# ProProject_STM32F103C6T6__2024-03-26.net
KiCad netlist of a schematic drawn in EasyEDA Pro
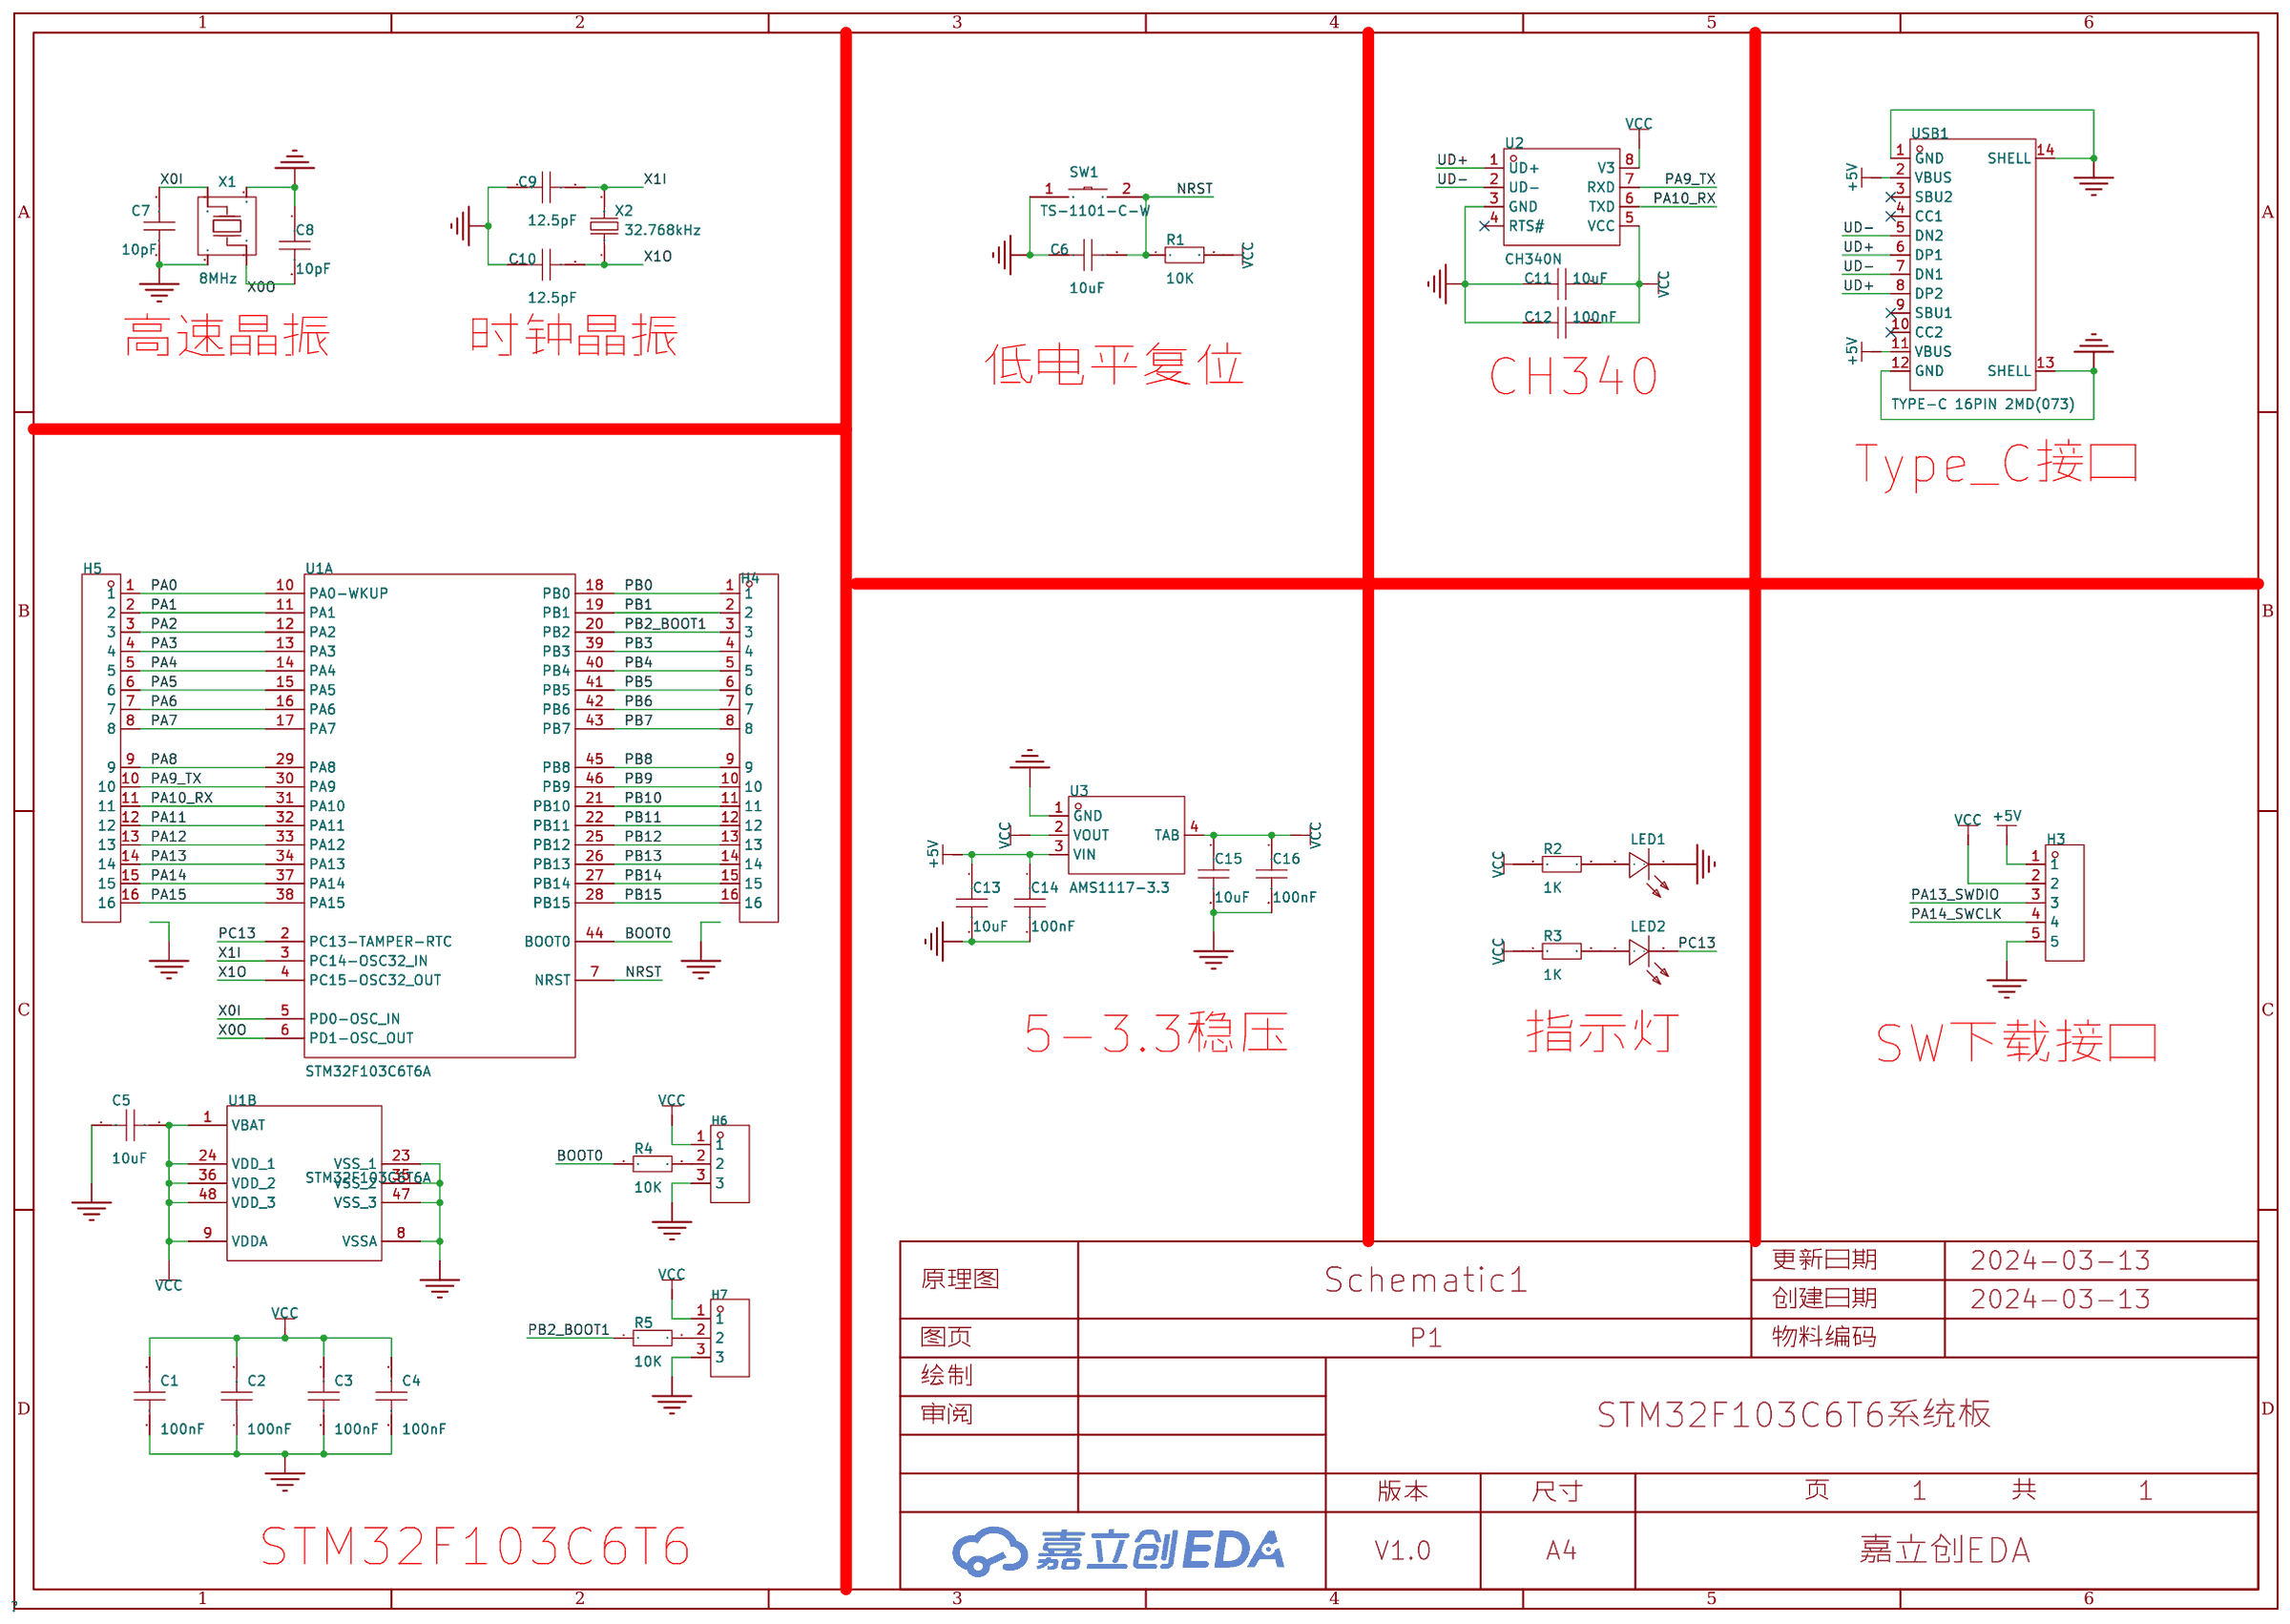
[diagram p0: schematic sheet]

(export (version "E")
  (design (tool "Eeschema 10.0.6"))
  (components
    (comp (ref "C1")
      (value "100nF")
      (footprint "easyedapro:C0603")
      (libsource (lib "easyedapro") (part "CapAcitance"))
    )
    (comp (ref "C2")
      (value "100nF")
      (footprint "easyedapro:C0603")
      (libsource (lib "easyedapro") (part "CapAcitance"))
    )
    (comp (ref "C3")
      (value "100nF")
      (footprint "easyedapro:C0603")
      (libsource (lib "easyedapro") (part "CapAcitance"))
    )
    (comp (ref "C4")
      (value "100nF")
      (footprint "easyedapro:C0603")
      (libsource (lib "easyedapro") (part "CapAcitance"))
    )
    (comp (ref "C5")
      (value "10uF")
      (footprint "easyedapro:C0603")
      (libsource (lib "easyedapro") (part "CapAcitance"))
    )
    (comp (ref "C6")
      (value "10uF")
      (footprint "easyedapro:C0603")
      (libsource (lib "easyedapro") (part "CapAcitance"))
    )
    (comp (ref "C7")
      (value "10pF")
      (footprint "easyedapro:C0603")
      (libsource (lib "easyedapro") (part "CapAcitance"))
    )
    (comp (ref "C8")
      (value "10pF")
      (footprint "easyedapro:C0603")
      (libsource (lib "easyedapro") (part "CapAcitance"))
    )
    (comp (ref "C9")
      (value "12.5pF")
      (footprint "easyedapro:C0603")
      (libsource (lib "easyedapro") (part "CapAcitance"))
    )
    (comp (ref "C10")
      (value "12.5pF")
      (footprint "easyedapro:C0603")
      (libsource (lib "easyedapro") (part "CapAcitance"))
    )
    (comp (ref "C11")
      (value "10uF")
      (footprint "easyedapro:C0603")
      (libsource (lib "easyedapro") (part "CapAcitance"))
    )
    (comp (ref "C12")
      (value "100nF")
      (footprint "easyedapro:C0603")
      (libsource (lib "easyedapro") (part "CapAcitance"))
    )
    (comp (ref "C13")
      (value "10uF")
      (footprint "easyedapro:C0603")
      (libsource (lib "easyedapro") (part "CapAcitance"))
    )
    (comp (ref "C14")
      (value "100nF")
      (footprint "easyedapro:C0603")
      (libsource (lib "easyedapro") (part "CapAcitance"))
    )
    (comp (ref "C15")
      (value "10uF")
      (footprint "easyedapro:C0603")
      (libsource (lib "easyedapro") (part "CapAcitance"))
    )
    (comp (ref "C16")
      (value "100nF")
      (footprint "easyedapro:C0603")
      (libsource (lib "easyedapro") (part "CapAcitance"))
    )
    (comp (ref "H3")
      (value "PZ254-1-05-W-8.5")
      (footprint "easyedapro:HDR-TH_5P-P2.54-H-M-W10.4-N")
      (fields (field (name "Manufacturer") "HCTL(华灿天禄)"))
      (libsource (lib "easyedapro") (part "PZ254-1-05-W-8.5"))
    )
    (comp (ref "H4")
      (value "X6511WV-20H-C60D30")
      (footprint "easyedapro:HDR-TH_20P-P2.54-V-M")
      (fields (field (name "Manufacturer") "XKB Connection(中国星坤)"))
      (libsource (lib "easyedapro") (part "X6511WV-20H-C30D60"))
    )
    (comp (ref "H5")
      (value "X6511WV-20H-C60D30")
      (footprint "easyedapro:HDR-TH_20P-P2.54-V-M")
      (fields (field (name "Manufacturer") "XKB Connection(中国星坤)"))
      (libsource (lib "easyedapro") (part "X6511WV-20H-C30D60"))
    )
    (comp (ref "H6")
      (value "PZ254V-11-03P")
      (footprint "easyedapro:HDR-TH_3P-P2.54-V-M")
      (fields (field (name "Manufacturer") "XFCN(兴飞)"))
      (libsource (lib "easyedapro") (part "PZ254V-11-03P_C2937625"))
    )
    (comp (ref "H7")
      (value "PZ254V-11-03P")
      (footprint "easyedapro:HDR-TH_3P-P2.54-V-M")
      (fields (field (name "Manufacturer") "XFCN(兴飞)"))
      (libsource (lib "easyedapro") (part "PZ254V-11-03P_C2937625"))
    )
    (comp (ref "LED1")
      (value "NCD0805R1")
      (footprint "easyedapro:LED0805-R-RD")
      (fields (field (name "Manufacturer") "国星光电"))
      (libsource (lib "easyedapro") (part "FC-2012HRK-620D"))
    )
    (comp (ref "LED2")
      (value "NCD0805R1")
      (footprint "easyedapro:LED0805-R-RD")
      (fields (field (name "Manufacturer") "国星光电"))
      (libsource (lib "easyedapro") (part "FC-2012HRK-620D"))
    )
    (comp (ref "R1") (value "10K") (footprint "easyedapro:R0603") (libsource (lib "easyedapro") (part "电阻")))
    (comp (ref "R2") (value "1K") (footprint "easyedapro:R0603") (libsource (lib "easyedapro") (part "电阻")))
    (comp (ref "R3") (value "1K") (footprint "easyedapro:R0603") (libsource (lib "easyedapro") (part "电阻")))
    (comp (ref "R4") (value "10K") (footprint "easyedapro:R0603") (libsource (lib "easyedapro") (part "电阻")))
    (comp (ref "R5") (value "10K") (footprint "easyedapro:R0603") (libsource (lib "easyedapro") (part "电阻")))
    (comp (ref "SW1")
      (value "TS-1101-C-W")
      (footprint "easyedapro:SW-SMD_L6.0-W3.3-LS8.0")
      (fields (field (name "Manufacturer") "XKB Connectivity(中国星坤)"))
      (libsource (lib "easyedapro") (part "TS-1101-C-W"))
    )
    (comp (ref "U1")
      (value "STM32F103C6T6A")
      (footprint "easyedapro:LQFP-48_L7.0-W7.0-P0.50-LS9.0-BL")
      (description "CPU内核:CM3;程序存储容量:32KB;RAM总容量:10KB;GPIO端口数量:37;工作电压范围:2V~3.6V;CPU最大主频:72MHz;程序存储器类型:FLASH;")
      (fields (field (name "Manufacturer") "ST(意法半导体)"))
      (libsource (lib "easyedapro") (part "STM32F103C6T6A"))
    )
    (comp (ref "U2")
      (value "CH340N")
      (footprint "easyedapro:SOP-8_L4.9-W3.9-P1.27-LS6.0-BL")
      (fields (field (name "Manufacturer") "WCH(南京沁恒)"))
      (libsource (lib "easyedapro") (part "CH340N_C2977777"))
    )
    (comp (ref "U3")
      (value "AMS1117-3.3")
      (footprint "easyedapro:SOT-223-3_L6.5-W3.5-P3.05-LS7.0")
      (description "输出类型：固定 输出极性：正 最大输入电压：18V 输出电压：3.3V 输出电流：1A 电源纹波抑制比(PSRR)：60dB@(120Hz)。当前应用较多领域：三端稳压器，机顶盒")
      (fields (field (name "Manufacturer") "TWGMC(台湾迪嘉)"))
      (libsource (lib "easyedapro") (part "AMS1117-3.3_C5250992"))
    )
    (comp (ref "USB1")
      (value "TYPE-C 16PIN 2MD(073)")
      (footprint "easyedapro:USB-C-SMD_TYPE-C-6PIN-2MD-073")
      (description "连接器类型:Type-C;标准:-;公母:母;端口数量:1;触点数量:16P;安装方式:卧贴;额定电流 - 电源:5A;工作温度范围:-25°C~+85°C;")
      (fields (field (name "Manufacturer") "SHOU HAN(首韩)"))
      (libsource (lib "easyedapro") (part "TYPE-C 16PIN 2MD(073)"))
    )
    (comp (ref "X1")
      (value "8MHz")
      (footprint "easyedapro:OSC-SMD_4P-L3.2-W2.5-BL")
      (description "晶振类型:贴片晶振;频率:8MHz;常温频差:±10ppm;外接负载电容:10pF;频率稳定度(全温):±15ppm;")
      (fields (field (name "Manufacturer Part") "TAXM8M4RDBCCT2T") (field (name "Manufacturer") "YJX(雅晶鑫)"))
      (libsource (lib "easyedapro") (part "TAXM8M4RDBCCT2T"))
    )
    (comp (ref "X2")
      (value "32.768kHz")
      (footprint "easyedapro:FC-135R_L3.2-W1.5")
      (description "晶振类型:贴片晶振;频率:32.768kHz;常温频差:±20ppm;外接负载电容:12.5pF;")
      (fields (field (name "Manufacturer Part") "Q13FC13500004") (field (name "Manufacturer") "EPSON(爱普生)"))
      (libsource (lib "easyedapro") (part "Q13FC1350000400"))
    )
  )
  (nets
    (net (code "1") (name "+5V") (class "Default")
      (node (ref "C13") (pin "1") (pinfunction "1_1") (pintype "input"))
      (node (ref "C14") (pin "1") (pinfunction "1_1") (pintype "input"))
      (node (ref "H3") (pin "1") (pinfunction "1_1") (pintype "unspecified"))
      (node (ref "U3") (pin "3") (pinfunction "VIN_3") (pintype "unspecified"))
      (node (ref "USB1") (pin "11") (pinfunction "VBUS_11") (pintype "unspecified"))
      (node (ref "USB1") (pin "2") (pinfunction "VBUS_2") (pintype "unspecified"))
    )
    (net (code "2") (name "/BOOT0") (class "Default")
      (node (ref "R4") (pin "1") (pinfunction "1_1") (pintype "input"))
      (node (ref "U1") (pin "44") (pinfunction "BOOT0_44") (pintype "unspecified"))
    )
    (net (code "3") (name "/NRST") (class "Default")
      (node (ref "C6") (pin "1") (pinfunction "1_1") (pintype "input"))
      (node (ref "R1") (pin "1") (pinfunction "1_1") (pintype "input"))
      (node (ref "SW1") (pin "2") (pinfunction "2_2") (pintype "unspecified"))
      (node (ref "U1") (pin "7") (pinfunction "NRST_7") (pintype "bidirectional"))
    )
    (net (code "4") (name "/PA0") (class "Default")
      (node (ref "H5") (pin "1") (pinfunction "1_1") (pintype "unspecified"))
      (node (ref "U1") (pin "10") (pinfunction "PA0-WKUP_10") (pintype "bidirectional"))
    )
    (net (code "5") (name "/PA1") (class "Default")
      (node (ref "H5") (pin "2") (pinfunction "2_2") (pintype "unspecified"))
      (node (ref "U1") (pin "11") (pinfunction "PA1_11") (pintype "bidirectional"))
    )
    (net (code "6") (name "/PA2") (class "Default")
      (node (ref "H5") (pin "3") (pinfunction "3_3") (pintype "unspecified"))
      (node (ref "U1") (pin "12") (pinfunction "PA2_12") (pintype "bidirectional"))
    )
    (net (code "7") (name "/PA3") (class "Default")
      (node (ref "H5") (pin "4") (pinfunction "4_4") (pintype "unspecified"))
      (node (ref "U1") (pin "13") (pinfunction "PA3_13") (pintype "bidirectional"))
    )
    (net (code "8") (name "/PA4") (class "Default")
      (node (ref "H5") (pin "5") (pinfunction "5_5") (pintype "unspecified"))
      (node (ref "U1") (pin "14") (pinfunction "PA4_14") (pintype "bidirectional"))
    )
    (net (code "9") (name "/PA5") (class "Default")
      (node (ref "H5") (pin "6") (pinfunction "6_6") (pintype "unspecified"))
      (node (ref "U1") (pin "15") (pinfunction "PA5_15") (pintype "bidirectional"))
    )
    (net (code "10") (name "/PA6") (class "Default")
      (node (ref "H5") (pin "7") (pinfunction "7_7") (pintype "unspecified"))
      (node (ref "U1") (pin "16") (pinfunction "PA6_16") (pintype "bidirectional"))
    )
    (net (code "11") (name "/PA7") (class "Default")
      (node (ref "H5") (pin "8") (pinfunction "8_8") (pintype "unspecified"))
      (node (ref "U1") (pin "17") (pinfunction "PA7_17") (pintype "bidirectional"))
    )
    (net (code "12") (name "/PA8") (class "Default")
      (node (ref "H5") (pin "9") (pinfunction "9_9") (pintype "unspecified"))
      (node (ref "U1") (pin "29") (pinfunction "PA8_29") (pintype "bidirectional"))
    )
    (net (code "13") (name "/PA9_TX") (class "Default")
      (node (ref "H5") (pin "10") (pinfunction "10_10") (pintype "unspecified"))
      (node (ref "U1") (pin "30") (pinfunction "PA9_30") (pintype "bidirectional"))
      (node (ref "U2") (pin "7") (pinfunction "RXD_7") (pintype "unspecified"))
    )
    (net (code "14") (name "/PA10_RX") (class "Default")
      (node (ref "H5") (pin "11") (pinfunction "11_11") (pintype "unspecified"))
      (node (ref "U1") (pin "31") (pinfunction "PA10_31") (pintype "bidirectional"))
      (node (ref "U2") (pin "6") (pinfunction "TXD_6") (pintype "unspecified"))
    )
    (net (code "15") (name "/PA11") (class "Default")
      (node (ref "H5") (pin "12") (pinfunction "12_12") (pintype "unspecified"))
      (node (ref "U1") (pin "32") (pinfunction "PA11_32") (pintype "bidirectional"))
    )
    (net (code "16") (name "/PA12") (class "Default")
      (node (ref "H5") (pin "13") (pinfunction "13_13") (pintype "unspecified"))
      (node (ref "U1") (pin "33") (pinfunction "PA12_33") (pintype "bidirectional"))
    )
    (net (code "17") (name "/PA13") (class "Default")
      (node (ref "H5") (pin "14") (pinfunction "14_14") (pintype "unspecified"))
      (node (ref "U1") (pin "34") (pinfunction "PA13_34") (pintype "bidirectional"))
    )
    (net (code "18") (name "/PA13_SWDIO") (class "Default")
      (node (ref "H3") (pin "3") (pinfunction "3_3") (pintype "unspecified"))
    )
    (net (code "19") (name "/PA14") (class "Default")
      (node (ref "H5") (pin "15") (pinfunction "15_15") (pintype "unspecified"))
      (node (ref "U1") (pin "37") (pinfunction "PA14_37") (pintype "bidirectional"))
    )
    (net (code "20") (name "/PA14_SWCLK") (class "Default")
      (node (ref "H3") (pin "4") (pinfunction "4_4") (pintype "unspecified"))
    )
    (net (code "21") (name "/PA15") (class "Default")
      (node (ref "H5") (pin "16") (pinfunction "16_16") (pintype "unspecified"))
      (node (ref "U1") (pin "38") (pinfunction "PA15_38") (pintype "bidirectional"))
    )
    (net (code "22") (name "/PB0") (class "Default")
      (node (ref "H4") (pin "1") (pinfunction "1_1") (pintype "unspecified"))
      (node (ref "U1") (pin "18") (pinfunction "PB0_18") (pintype "bidirectional"))
    )
    (net (code "23") (name "/PB1") (class "Default")
      (node (ref "H4") (pin "2") (pinfunction "2_2") (pintype "unspecified"))
      (node (ref "U1") (pin "19") (pinfunction "PB1_19") (pintype "bidirectional"))
    )
    (net (code "24") (name "/PB2_BOOT1") (class "Default")
      (node (ref "H4") (pin "3") (pinfunction "3_3") (pintype "unspecified"))
      (node (ref "R5") (pin "1") (pinfunction "1_1") (pintype "input"))
      (node (ref "U1") (pin "20") (pinfunction "PB2_20") (pintype "bidirectional"))
    )
    (net (code "25") (name "/PB3") (class "Default")
      (node (ref "H4") (pin "4") (pinfunction "4_4") (pintype "unspecified"))
      (node (ref "U1") (pin "39") (pinfunction "PB3_39") (pintype "bidirectional"))
    )
    (net (code "26") (name "/PB4") (class "Default")
      (node (ref "H4") (pin "5") (pinfunction "5_5") (pintype "unspecified"))
      (node (ref "U1") (pin "40") (pinfunction "PB4_40") (pintype "bidirectional"))
    )
    (net (code "27") (name "/PB5") (class "Default")
      (node (ref "H4") (pin "6") (pinfunction "6_6") (pintype "unspecified"))
      (node (ref "U1") (pin "41") (pinfunction "PB5_41") (pintype "bidirectional"))
    )
    (net (code "28") (name "/PB6") (class "Default")
      (node (ref "H4") (pin "7") (pinfunction "7_7") (pintype "unspecified"))
      (node (ref "U1") (pin "42") (pinfunction "PB6_42") (pintype "bidirectional"))
    )
    (net (code "29") (name "/PB7") (class "Default")
      (node (ref "H4") (pin "8") (pinfunction "8_8") (pintype "unspecified"))
      (node (ref "U1") (pin "43") (pinfunction "PB7_43") (pintype "bidirectional"))
    )
    (net (code "30") (name "/PB8") (class "Default")
      (node (ref "H4") (pin "9") (pinfunction "9_9") (pintype "unspecified"))
      (node (ref "U1") (pin "45") (pinfunction "PB8_45") (pintype "bidirectional"))
    )
    (net (code "31") (name "/PB9") (class "Default")
      (node (ref "H4") (pin "10") (pinfunction "10_10") (pintype "unspecified"))
      (node (ref "U1") (pin "46") (pinfunction "PB9_46") (pintype "bidirectional"))
    )
    (net (code "32") (name "/PB10") (class "Default")
      (node (ref "H4") (pin "11") (pinfunction "11_11") (pintype "unspecified"))
      (node (ref "U1") (pin "21") (pinfunction "PB10_21") (pintype "bidirectional"))
    )
    (net (code "33") (name "/PB11") (class "Default")
      (node (ref "H4") (pin "12") (pinfunction "12_12") (pintype "unspecified"))
      (node (ref "U1") (pin "22") (pinfunction "PB11_22") (pintype "bidirectional"))
    )
    (net (code "34") (name "/PB12") (class "Default")
      (node (ref "H4") (pin "13") (pinfunction "13_13") (pintype "unspecified"))
      (node (ref "U1") (pin "25") (pinfunction "PB12_25") (pintype "bidirectional"))
    )
    (net (code "35") (name "/PB13") (class "Default")
      (node (ref "H4") (pin "14") (pinfunction "14_14") (pintype "unspecified"))
      (node (ref "U1") (pin "26") (pinfunction "PB13_26") (pintype "bidirectional"))
    )
    (net (code "36") (name "/PB14") (class "Default")
      (node (ref "H4") (pin "15") (pinfunction "15_15") (pintype "unspecified"))
      (node (ref "U1") (pin "27") (pinfunction "PB14_27") (pintype "bidirectional"))
    )
    (net (code "37") (name "/PB15") (class "Default")
      (node (ref "H4") (pin "16") (pinfunction "16_16") (pintype "unspecified"))
      (node (ref "U1") (pin "28") (pinfunction "PB15_28") (pintype "bidirectional"))
    )
    (net (code "38") (name "/PC13") (class "Default")
      (node (ref "LED2") (pin "2") (pinfunction "-_2") (pintype "unspecified"))
      (node (ref "U1") (pin "2") (pinfunction "PC13-TAMPER-RTC_2") (pintype "bidirectional"))
    )
    (net (code "39") (name "/UD+") (class "Default")
      (node (ref "U2") (pin "1") (pinfunction "UD+_1") (pintype "unspecified"))
      (node (ref "USB1") (pin "6") (pinfunction "DP1_6") (pintype "unspecified"))
      (node (ref "USB1") (pin "8") (pinfunction "DP2_8") (pintype "unspecified"))
    )
    (net (code "40") (name "/UD-") (class "Default")
      (node (ref "U2") (pin "2") (pinfunction "UD-_2") (pintype "unspecified"))
      (node (ref "USB1") (pin "5") (pinfunction "DN2_5") (pintype "unspecified"))
      (node (ref "USB1") (pin "7") (pinfunction "DN1_7") (pintype "unspecified"))
    )
    (net (code "41") (name "/X0I") (class "Default")
      (node (ref "C7") (pin "1") (pinfunction "1_1") (pintype "input"))
      (node (ref "U1") (pin "5") (pinfunction "PD0-OSC_IN_5") (pintype "bidirectional"))
      (node (ref "X1") (pin "3") (pinfunction "3_3") (pintype "input"))
    )
    (net (code "42") (name "/X0O") (class "Default")
      (node (ref "C8") (pin "2") (pinfunction "2_2") (pintype "input"))
      (node (ref "U1") (pin "6") (pinfunction "PD1-OSC_OUT_6") (pintype "bidirectional"))
      (node (ref "X1") (pin "1") (pinfunction "1_1") (pintype "input"))
    )
    (net (code "43") (name "/X1I") (class "Default")
      (node (ref "C9") (pin "2") (pinfunction "2_2") (pintype "input"))
      (node (ref "U1") (pin "3") (pinfunction "PC14-OSC32_IN_3") (pintype "bidirectional"))
      (node (ref "X2") (pin "2") (pinfunction "2_2") (pintype "unspecified"))
    )
    (net (code "44") (name "/X1O") (class "Default")
      (node (ref "C10") (pin "2") (pinfunction "2_2") (pintype "input"))
      (node (ref "U1") (pin "4") (pinfunction "PC15-OSC32_OUT_4") (pintype "bidirectional"))
      (node (ref "X2") (pin "1") (pinfunction "1_1") (pintype "unspecified"))
    )
    (net (code "45") (name "GND") (class "Default")
      (node (ref "C1") (pin "1") (pinfunction "1_1") (pintype "input"))
      (node (ref "C10") (pin "1") (pinfunction "1_1") (pintype "input"))
      (node (ref "C11") (pin "1") (pinfunction "1_1") (pintype "input"))
      (node (ref "C12") (pin "1") (pinfunction "1_1") (pintype "input"))
      (node (ref "C13") (pin "2") (pinfunction "2_2") (pintype "input"))
      (node (ref "C14") (pin "2") (pinfunction "2_2") (pintype "input"))
      (node (ref "C15") (pin "2") (pinfunction "2_2") (pintype "input"))
      (node (ref "C16") (pin "2") (pinfunction "2_2") (pintype "input"))
      (node (ref "C2") (pin "1") (pinfunction "1_1") (pintype "input"))
      (node (ref "C3") (pin "1") (pinfunction "1_1") (pintype "input"))
      (node (ref "C4") (pin "1") (pinfunction "1_1") (pintype "input"))
      (node (ref "C5") (pin "2") (pinfunction "2_2") (pintype "input"))
      (node (ref "C6") (pin "2") (pinfunction "2_2") (pintype "input"))
      (node (ref "C7") (pin "2") (pinfunction "2_2") (pintype "input"))
      (node (ref "C8") (pin "1") (pinfunction "1_1") (pintype "input"))
      (node (ref "C9") (pin "1") (pinfunction "1_1") (pintype "input"))
      (node (ref "H3") (pin "5") (pinfunction "5_5") (pintype "unspecified"))
      (node (ref "H6") (pin "3") (pinfunction "3_3") (pintype "input"))
      (node (ref "H7") (pin "3") (pinfunction "3_3") (pintype "input"))
      (node (ref "LED1") (pin "2") (pinfunction "-_2") (pintype "unspecified"))
      (node (ref "SW1") (pin "1") (pinfunction "1_1") (pintype "unspecified"))
      (node (ref "U1") (pin "23") (pinfunction "VSS_1_23") (pintype "unspecified"))
      (node (ref "U1") (pin "35") (pinfunction "VSS_2_35") (pintype "unspecified"))
      (node (ref "U1") (pin "47") (pinfunction "VSS_3_47") (pintype "unspecified"))
      (node (ref "U1") (pin "8") (pinfunction "VSSA_8") (pintype "unspecified"))
      (node (ref "U2") (pin "3") (pinfunction "GND_3") (pintype "unspecified"))
      (node (ref "U3") (pin "1") (pinfunction "GND_1") (pintype "unspecified"))
      (node (ref "USB1") (pin "1") (pinfunction "GND_1") (pintype "unspecified"))
      (node (ref "USB1") (pin "12") (pinfunction "GND_12") (pintype "unspecified"))
      (node (ref "USB1") (pin "13") (pinfunction "SHELL_13") (pintype "unspecified"))
      (node (ref "USB1") (pin "14") (pinfunction "SHELL_14") (pintype "unspecified"))
      (node (ref "X1") (pin "2") (pinfunction "2_2") (pintype "input"))
      (node (ref "X1") (pin "4") (pinfunction "4_4") (pintype "input"))
    )
    (net (code "46") (name "Net-(H6-Pad2)") (class "Default")
      (node (ref "H6") (pin "2") (pinfunction "2_2") (pintype "input"))
      (node (ref "R4") (pin "2") (pinfunction "2_2") (pintype "input"))
    )
    (net (code "47") (name "Net-(H7-Pad2)") (class "Default")
      (node (ref "H7") (pin "2") (pinfunction "2_2") (pintype "input"))
      (node (ref "R5") (pin "2") (pinfunction "2_2") (pintype "input"))
    )
    (net (code "48") (name "Net-(LED1-+)") (class "Default")
      (node (ref "LED1") (pin "1") (pinfunction "+_1") (pintype "unspecified"))
      (node (ref "R2") (pin "2") (pinfunction "2_2") (pintype "input"))
    )
    (net (code "49") (name "Net-(LED2-+)") (class "Default")
      (node (ref "LED2") (pin "1") (pinfunction "+_1") (pintype "unspecified"))
      (node (ref "R3") (pin "2") (pinfunction "2_2") (pintype "input"))
    )
    (net (code "50") (name "VCC") (class "Default")
      (node (ref "C1") (pin "2") (pinfunction "2_2") (pintype "input"))
      (node (ref "C11") (pin "2") (pinfunction "2_2") (pintype "input"))
      (node (ref "C12") (pin "2") (pinfunction "2_2") (pintype "input"))
      (node (ref "C15") (pin "1") (pinfunction "1_1") (pintype "input"))
      (node (ref "C16") (pin "1") (pinfunction "1_1") (pintype "input"))
      (node (ref "C2") (pin "2") (pinfunction "2_2") (pintype "input"))
      (node (ref "C3") (pin "2") (pinfunction "2_2") (pintype "input"))
      (node (ref "C4") (pin "2") (pinfunction "2_2") (pintype "input"))
      (node (ref "C5") (pin "1") (pinfunction "1_1") (pintype "input"))
      (node (ref "H3") (pin "2") (pinfunction "2_2") (pintype "unspecified"))
      (node (ref "H6") (pin "1") (pinfunction "1_1") (pintype "input"))
      (node (ref "H7") (pin "1") (pinfunction "1_1") (pintype "input"))
      (node (ref "R1") (pin "2") (pinfunction "2_2") (pintype "input"))
      (node (ref "R2") (pin "1") (pinfunction "1_1") (pintype "input"))
      (node (ref "R3") (pin "1") (pinfunction "1_1") (pintype "input"))
      (node (ref "U1") (pin "1") (pinfunction "VBAT_1") (pintype "unspecified"))
      (node (ref "U1") (pin "24") (pinfunction "VDD_1_24") (pintype "unspecified"))
      (node (ref "U1") (pin "36") (pinfunction "VDD_2_36") (pintype "unspecified"))
      (node (ref "U1") (pin "48") (pinfunction "VDD_3_48") (pintype "unspecified"))
      (node (ref "U1") (pin "9") (pinfunction "VDDA_9") (pintype "unspecified"))
      (node (ref "U2") (pin "5") (pinfunction "VCC_5") (pintype "unspecified"))
      (node (ref "U2") (pin "8") (pinfunction "V3_8") (pintype "unspecified"))
      (node (ref "U3") (pin "2") (pinfunction "VOUT_2") (pintype "unspecified"))
      (node (ref "U3") (pin "4") (pinfunction "TAB_4") (pintype "unspecified"))
    )
    (net (code "51") (name "unconnected-(U2-RTS#-Pad4)") (class "Default")
      (node (ref "U2") (pin "4") (pinfunction "RTS#_4") (pintype "unspecified+no_connect"))
    )
    (net (code "52") (name "unconnected-(USB1-CC1-Pad4)") (class "Default")
      (node (ref "USB1") (pin "4") (pinfunction "CC1_4") (pintype "unspecified+no_connect"))
    )
    (net (code "53") (name "unconnected-(USB1-CC2-Pad10)") (class "Default")
      (node (ref "USB1") (pin "10") (pinfunction "CC2_10") (pintype "unspecified+no_connect"))
    )
    (net (code "54") (name "unconnected-(USB1-SBU1-Pad9)") (class "Default")
      (node (ref "USB1") (pin "9") (pinfunction "SBU1_9") (pintype "unspecified+no_connect"))
    )
    (net (code "55") (name "unconnected-(USB1-SBU2-Pad3)") (class "Default")
      (node (ref "USB1") (pin "3") (pinfunction "SBU2_3") (pintype "unspecified+no_connect"))
    )
  )
)
